# PCB-SCH_mvs.net
KiCad netlist of a schematic drawn in EAGLE
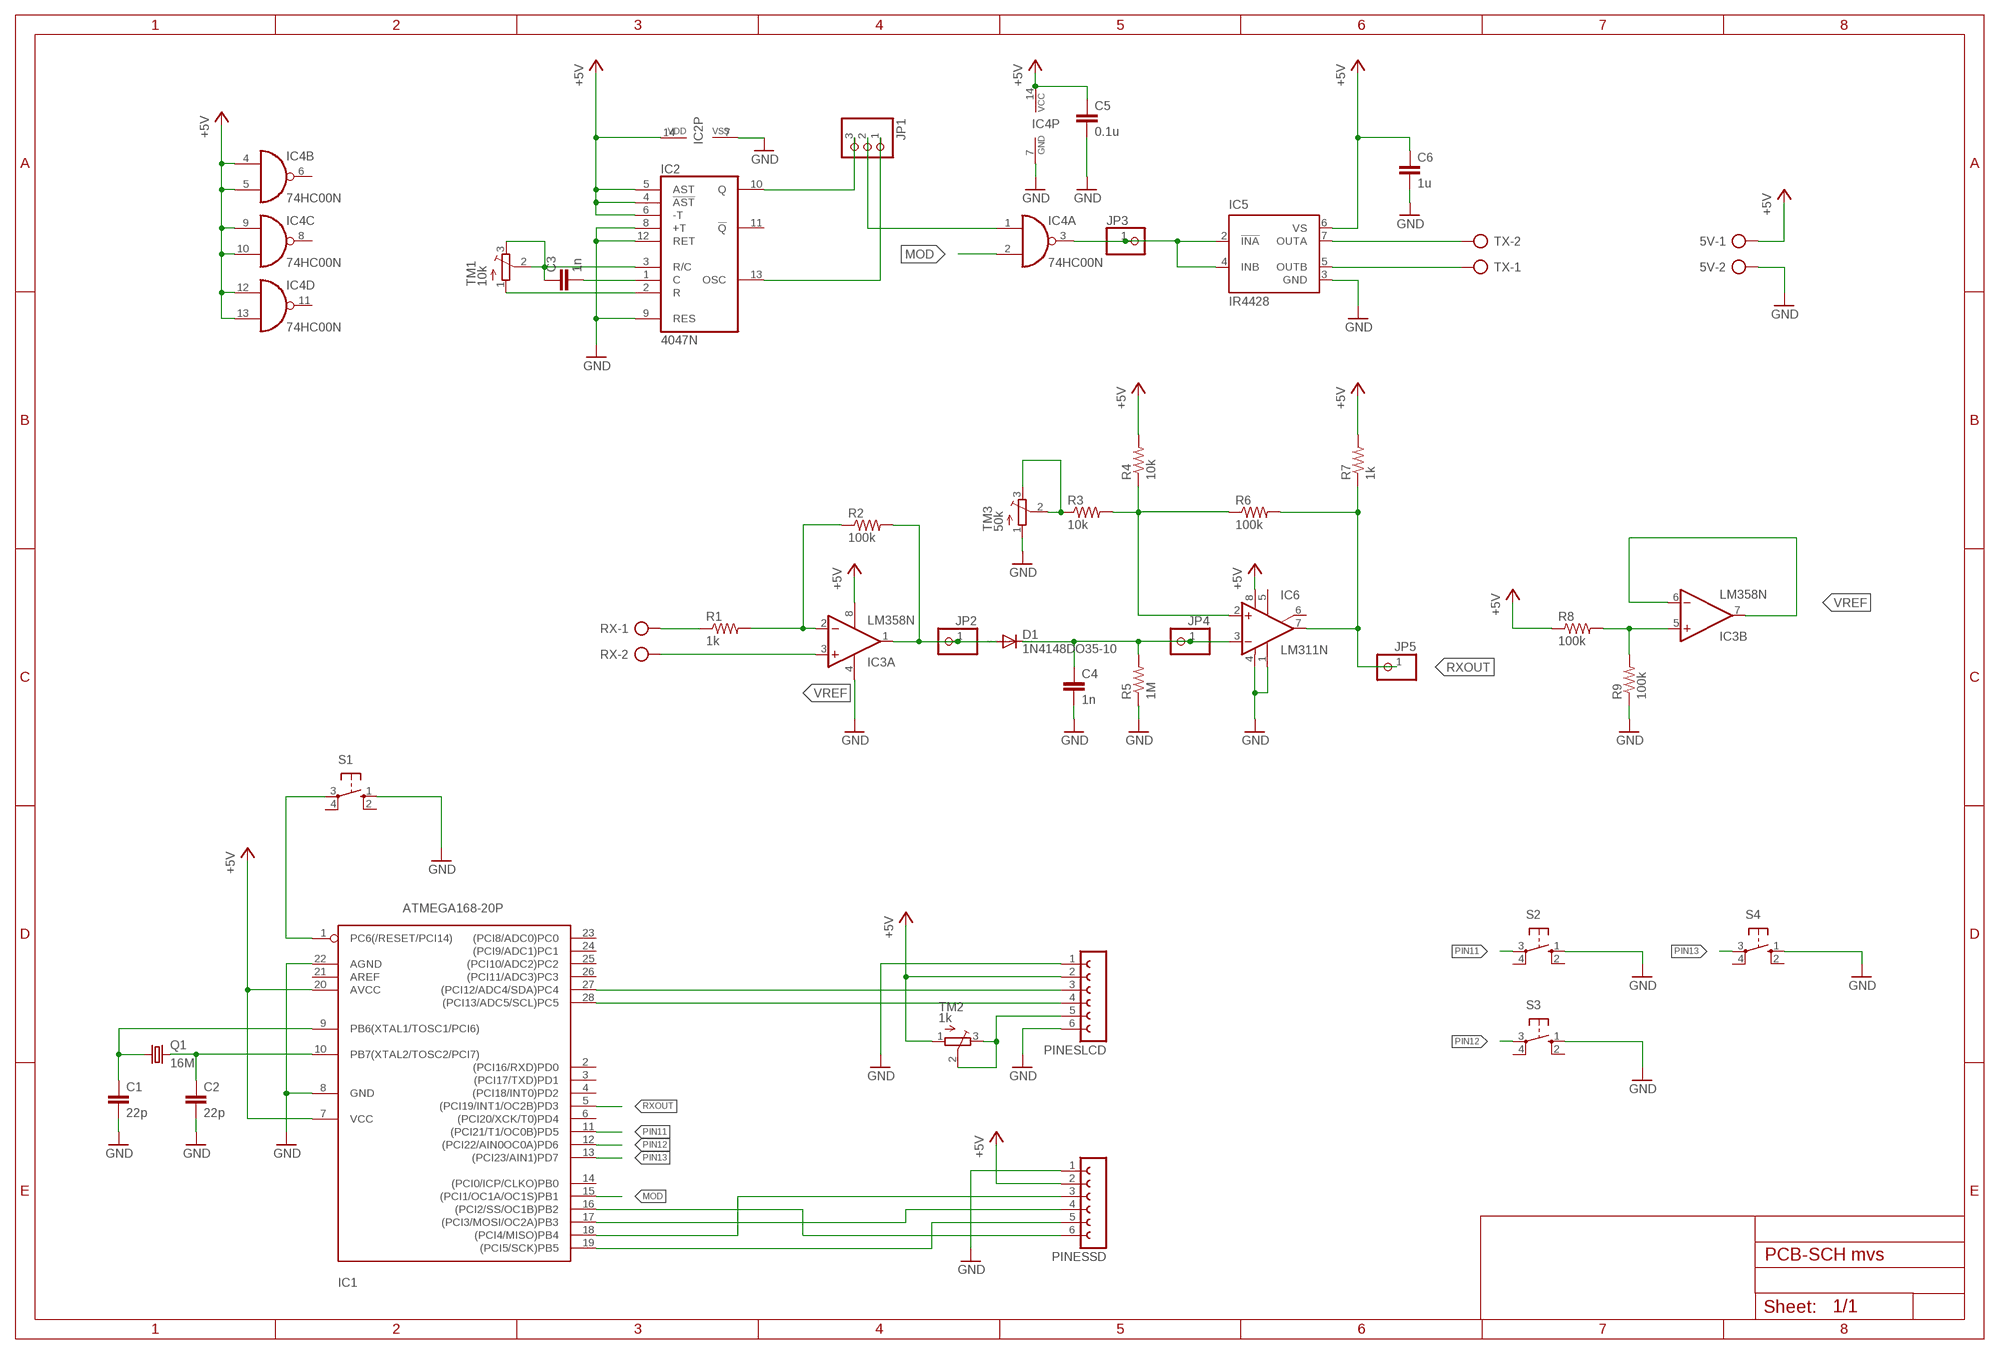
[diagram p0: schematic, sheet 1]

(export (version "E")
  (design (tool "Eeschema 10.0.6"))
  (components
    (comp (ref "5V")
      (value "AK500/2")
      (footprint "eagle-import:AK500_2")
      (libsource (lib "eagle-import") (part "AK500/2"))
    )
    (comp (ref "C1")
      (value "22p")
      (footprint "eagle-import:C050-024X044")
      (libsource (lib "eagle-import") (part "C-EU050-024X044"))
    )
    (comp (ref "C2")
      (value "22p")
      (footprint "eagle-import:C050-024X044")
      (libsource (lib "eagle-import") (part "C-EU050-024X044"))
    )
    (comp (ref "C3")
      (value "1n")
      (footprint "eagle-import:C050-024X044")
      (libsource (lib "eagle-import") (part "C-EU050-024X044"))
    )
    (comp (ref "C4")
      (value "1n")
      (footprint "eagle-import:C050-024X044")
      (libsource (lib "eagle-import") (part "C-EU050-024X044"))
    )
    (comp (ref "C5")
      (value "0.1u")
      (footprint "eagle-import:C050-024X044")
      (libsource (lib "eagle-import") (part "C-EU050-024X044"))
    )
    (comp (ref "C6")
      (value "1u")
      (footprint "eagle-import:C050-024X044")
      (libsource (lib "eagle-import") (part "C-EU050-024X044"))
    )
    (comp (ref "D1")
      (value "1N4148DO35-10")
      (footprint "eagle-import:DO35-10")
      (libsource (lib "eagle-import") (part "1N4148DO35-10"))
    )
    (comp (ref "IC1")
      (value "ATMEGA168-20P")
      (footprint "eagle-import:DIL28-3")
      (libsource (lib "eagle-import") (part "ATMEGA168P-20"))
    )
    (comp (ref "IC2")
      (value "4047N")
      (footprint "eagle-import:DIL14")
      (libsource (lib "eagle-import") (part "4047N"))
    )
    (comp (ref "IC3")
      (value "LM358N")
      (footprint "eagle-import:DIL08")
      (libsource (lib "eagle-import") (part "LM358N"))
    )
    (comp (ref "IC4")
      (value "74HC00N")
      (footprint "eagle-import:DIL14")
      (libsource (lib "eagle-import") (part "7400NHC"))
    )
    (comp (ref "IC5")
      (value "IR4428")
      (footprint "eagle-import:DIL08")
      (fields (field (name "MF") "INTERNATIONAL RECTIFIER(IR)") (field (name "MPN") "IR4428PBF"))
      (libsource (lib "eagle-import") (part "IR4428"))
    )
    (comp (ref "IC6")
      (value "LM311N")
      (footprint "eagle-import:DIL08")
      (libsource (lib "eagle-import") (part "LM311N"))
    )
    (comp (ref "JP1")
      (value "PINHD-1X3")
      (footprint "eagle-import:1X03")
      (libsource (lib "eagle-import") (part "PINHD-1X3"))
    )
    (comp (ref "JP2")
      (value "PINHD-1X1")
      (footprint "eagle-import:1X01")
      (libsource (lib "eagle-import") (part "PINHD-1X1"))
    )
    (comp (ref "JP3")
      (value "PINHD-1X1")
      (footprint "eagle-import:1X01")
      (libsource (lib "eagle-import") (part "PINHD-1X1"))
    )
    (comp (ref "JP4")
      (value "PINHD-1X1")
      (footprint "eagle-import:1X01")
      (libsource (lib "eagle-import") (part "PINHD-1X1"))
    )
    (comp (ref "JP5")
      (value "PINHD-1X1")
      (footprint "eagle-import:1X01")
      (libsource (lib "eagle-import") (part "PINHD-1X1"))
    )
    (comp (ref "PINESLCD")
      (value "FE06-1")
      (footprint "eagle-import:FE06")
      (libsource (lib "eagle-import") (part "FE06-1"))
    )
    (comp (ref "PINESSD")
      (value "FE06-1")
      (footprint "eagle-import:FE06")
      (libsource (lib "eagle-import") (part "FE06-1"))
    )
    (comp (ref "Q1")
      (value "16M")
      (footprint "eagle-import:HC49U-V")
      (libsource (lib "eagle-import") (part "CRYSTALHC49U-V"))
    )
    (comp (ref "R1")
      (value "1k")
      (footprint "eagle-import:0207_10")
      (libsource (lib "eagle-import") (part "R-US_0207/10"))
    )
    (comp (ref "R2")
      (value "100k")
      (footprint "eagle-import:0207_10")
      (libsource (lib "eagle-import") (part "R-US_0207/10"))
    )
    (comp (ref "R3")
      (value "10k")
      (footprint "eagle-import:0207_10")
      (libsource (lib "eagle-import") (part "R-US_0207/10"))
    )
    (comp (ref "R4")
      (value "10k")
      (footprint "eagle-import:0207_10")
      (libsource (lib "eagle-import") (part "R-US_0207/10"))
    )
    (comp (ref "R5")
      (value "1M")
      (footprint "eagle-import:0207_10")
      (libsource (lib "eagle-import") (part "R-US_0207/10"))
    )
    (comp (ref "R6")
      (value "100k")
      (footprint "eagle-import:0207_10")
      (libsource (lib "eagle-import") (part "R-US_0207/10"))
    )
    (comp (ref "R7")
      (value "1k")
      (footprint "eagle-import:0207_10")
      (libsource (lib "eagle-import") (part "R-US_0207/10"))
    )
    (comp (ref "R8")
      (value "100k")
      (footprint "eagle-import:0207_10")
      (libsource (lib "eagle-import") (part "R-US_0207/10"))
    )
    (comp (ref "R9")
      (value "100k")
      (footprint "eagle-import:0207_10")
      (libsource (lib "eagle-import") (part "R-US_0207/10"))
    )
    (comp (ref "RX")
      (value "AK500/2")
      (footprint "eagle-import:AK500_2")
      (libsource (lib "eagle-import") (part "AK500/2"))
    )
    (comp (ref "S1")
      (value "10-XX")
      (footprint "eagle-import:B3F-10XX")
      (fields (field (name "MPN") "B3F-1000"))
      (libsource (lib "eagle-import") (part "10-XX"))
    )
    (comp (ref "S2")
      (value "10-XX")
      (footprint "eagle-import:B3F-10XX")
      (fields (field (name "MPN") "B3F-1000"))
      (libsource (lib "eagle-import") (part "10-XX"))
    )
    (comp (ref "S3")
      (value "10-XX")
      (footprint "eagle-import:B3F-10XX")
      (fields (field (name "MPN") "B3F-1000"))
      (libsource (lib "eagle-import") (part "10-XX"))
    )
    (comp (ref "S4")
      (value "10-XX")
      (footprint "eagle-import:B3F-10XX")
      (fields (field (name "MPN") "B3F-1000"))
      (libsource (lib "eagle-import") (part "10-XX"))
    )
    (comp (ref "TM1")
      (value "10k")
      (footprint "eagle-import:TRIM-3386")
      (libsource (lib "eagle-import") (part "TRIMPOT3386"))
    )
    (comp (ref "TM2")
      (value "1k")
      (footprint "eagle-import:TRIM-3386")
      (libsource (lib "eagle-import") (part "TRIMPOT3386"))
    )
    (comp (ref "TM3")
      (value "50k")
      (footprint "eagle-import:TRIM-3386")
      (libsource (lib "eagle-import") (part "TRIMPOT3386"))
    )
    (comp (ref "TX")
      (value "AK500/2")
      (footprint "eagle-import:AK500_2")
      (libsource (lib "eagle-import") (part "AK500/2"))
    )
  )
  (nets
    (net (code "1") (name "+5V") (class "Default")
      (node (ref "5V") (pin "1") (pinfunction "KL_1") (pintype "passive"))
      (node (ref "C5") (pin "1") (pinfunction "1_1") (pintype "passive"))
      (node (ref "C6") (pin "1") (pinfunction "1_1") (pintype "passive"))
      (node (ref "IC1") (pin "20") (pinfunction "AVCC_20") (pintype "bidirectional"))
      (node (ref "IC1") (pin "7") (pinfunction "VCC_7") (pintype "bidirectional"))
      (node (ref "IC2") (pin "14") (pinfunction "VDD_14") (pintype "power_in"))
      (node (ref "IC2") (pin "4") (pinfunction "~{AST}_4") (pintype "input"))
      (node (ref "IC2") (pin "5") (pinfunction "AST_5") (pintype "input"))
      (node (ref "IC2") (pin "6") (pinfunction "-T_6") (pintype "input"))
      (node (ref "IC3") (pin "8") (pinfunction "V+_8") (pintype "power_in"))
      (node (ref "IC4") (pin "10") (pinfunction "I1_10") (pintype "input"))
      (node (ref "IC4") (pin "12") (pinfunction "I0_12") (pintype "input"))
      (node (ref "IC4") (pin "13") (pinfunction "I1_13") (pintype "input"))
      (node (ref "IC4") (pin "14") (pinfunction "VCC_14") (pintype "power_in"))
      (node (ref "IC4") (pin "4") (pinfunction "I0_4") (pintype "input"))
      (node (ref "IC4") (pin "5") (pinfunction "I1_5") (pintype "input"))
      (node (ref "IC4") (pin "9") (pinfunction "I0_9") (pintype "input"))
      (node (ref "IC5") (pin "6") (pinfunction "VS_6") (pintype "power_in"))
      (node (ref "IC6") (pin "8") (pinfunction "V+_8") (pintype "power_in"))
      (node (ref "PINESLCD") (pin "2") (pinfunction "2_2") (pintype "passive"))
      (node (ref "PINESSD") (pin "2") (pinfunction "2_2") (pintype "passive"))
      (node (ref "R4") (pin "2") (pinfunction "2_2") (pintype "passive"))
      (node (ref "R7") (pin "2") (pinfunction "2_2") (pintype "passive"))
      (node (ref "R8") (pin "1") (pinfunction "1_1") (pintype "passive"))
      (node (ref "TM2") (pin "1") (pinfunction "A_1") (pintype "passive"))
    )
    (net (code "2") (name "GND") (class "Default")
      (node (ref "5V") (pin "2") (pinfunction "KL_2") (pintype "passive"))
      (node (ref "C1") (pin "2") (pinfunction "2_2") (pintype "passive"))
      (node (ref "C2") (pin "2") (pinfunction "2_2") (pintype "passive"))
      (node (ref "C4") (pin "2") (pinfunction "2_2") (pintype "passive"))
      (node (ref "C5") (pin "2") (pinfunction "2_2") (pintype "passive"))
      (node (ref "C6") (pin "2") (pinfunction "2_2") (pintype "passive"))
      (node (ref "IC1") (pin "22") (pinfunction "AGND_22") (pintype "bidirectional"))
      (node (ref "IC1") (pin "8") (pinfunction "GND_8") (pintype "bidirectional"))
      (node (ref "IC2") (pin "12") (pinfunction "RET_12") (pintype "input"))
      (node (ref "IC2") (pin "7") (pinfunction "VSS_7") (pintype "power_in"))
      (node (ref "IC2") (pin "8") (pinfunction "+T_8") (pintype "input"))
      (node (ref "IC2") (pin "9") (pinfunction "RES_9") (pintype "input"))
      (node (ref "IC3") (pin "4") (pinfunction "V-_4") (pintype "power_in"))
      (node (ref "IC4") (pin "7") (pinfunction "GND_7") (pintype "power_in"))
      (node (ref "IC5") (pin "3") (pinfunction "GND_3") (pintype "power_in"))
      (node (ref "IC6") (pin "1") (pinfunction "GND_1") (pintype "passive"))
      (node (ref "IC6") (pin "4") (pinfunction "V-_4") (pintype "power_in"))
      (node (ref "PINESLCD") (pin "1") (pinfunction "1_1") (pintype "passive"))
      (node (ref "PINESLCD") (pin "6") (pinfunction "6_6") (pintype "passive"))
      (node (ref "PINESSD") (pin "1") (pinfunction "1_1") (pintype "passive"))
      (node (ref "R5") (pin "1") (pinfunction "1_1") (pintype "passive"))
      (node (ref "R9") (pin "1") (pinfunction "1_1") (pintype "passive"))
      (node (ref "S1") (pin "1") (pinfunction "S_1") (pintype "passive"))
      (node (ref "S2") (pin "1") (pinfunction "S_1") (pintype "passive"))
      (node (ref "S3") (pin "1") (pinfunction "S_1") (pintype "passive"))
      (node (ref "S4") (pin "1") (pinfunction "S_1") (pintype "passive"))
      (node (ref "TM3") (pin "1") (pinfunction "A_1") (pintype "passive"))
    )
    (net (code "3") (name "MOD") (class "Default")
      (node (ref "IC1") (pin "15") (pinfunction "(PCI1/OC1A/OC1S)PB1_15") (pintype "bidirectional"))
      (node (ref "IC4") (pin "2") (pinfunction "I1_2") (pintype "input"))
    )
    (net (code "4") (name "Net-(IC1-(PCI2{slash}SS{slash}OC1B)PB2)") (class "Default")
      (node (ref "IC1") (pin "16") (pinfunction "(PCI2/SS/OC1B)PB2_16") (pintype "bidirectional"))
      (node (ref "PINESSD") (pin "6") (pinfunction "6_6") (pintype "passive"))
    )
    (net (code "5") (name "Net-(IC1-(PCI3{slash}MOSI{slash}OC2A)PB3)") (class "Default")
      (node (ref "IC1") (pin "17") (pinfunction "(PCI3/MOSI/OC2A)PB3_17") (pintype "bidirectional"))
      (node (ref "PINESSD") (pin "4") (pinfunction "4_4") (pintype "passive"))
    )
    (net (code "6") (name "Net-(IC1-(PCI4{slash}MISO)PB4)") (class "Default")
      (node (ref "IC1") (pin "18") (pinfunction "(PCI4/MISO)PB4_18") (pintype "bidirectional"))
      (node (ref "PINESSD") (pin "3") (pinfunction "3_3") (pintype "passive"))
    )
    (net (code "7") (name "Net-(IC1-(PCI5{slash}SCK)PB5)") (class "Default")
      (node (ref "IC1") (pin "19") (pinfunction "(PCI5/SCK)PB5_19") (pintype "bidirectional"))
      (node (ref "PINESSD") (pin "5") (pinfunction "5_5") (pintype "passive"))
    )
    (net (code "8") (name "Net-(IC1-(PCI12{slash}ADC4{slash}SDA)PC4)") (class "Default")
      (node (ref "IC1") (pin "27") (pinfunction "(PCI12/ADC4/SDA)PC4_27") (pintype "bidirectional"))
      (node (ref "PINESLCD") (pin "3") (pinfunction "3_3") (pintype "passive"))
    )
    (net (code "9") (name "Net-(IC1-(PCI13{slash}ADC5{slash}SCL)PC5)") (class "Default")
      (node (ref "IC1") (pin "28") (pinfunction "(PCI13/ADC5/SCL)PC5_28") (pintype "bidirectional"))
      (node (ref "PINESLCD") (pin "4") (pinfunction "4_4") (pintype "passive"))
    )
    (net (code "10") (name "Net-(IC1-PB6(XTAL1{slash}TOSC1{slash}PCI6))") (class "Default")
      (node (ref "C1") (pin "1") (pinfunction "1_1") (pintype "passive"))
      (node (ref "IC1") (pin "9") (pinfunction "PB6(XTAL1/TOSC1/PCI6)_9") (pintype "bidirectional"))
      (node (ref "Q1") (pin "1") (pinfunction "1_1") (pintype "passive"))
    )
    (net (code "11") (name "Net-(IC1-PB7(XTAL2{slash}TOSC2{slash}PCI7))") (class "Default")
      (node (ref "C2") (pin "1") (pinfunction "1_1") (pintype "passive"))
      (node (ref "IC1") (pin "10") (pinfunction "PB7(XTAL2/TOSC2/PCI7)_10") (pintype "bidirectional"))
      (node (ref "Q1") (pin "2") (pinfunction "2_2") (pintype "passive"))
    )
    (net (code "12") (name "Net-(IC1-PC6({slash}RESET{slash}PCI14))") (class "Default")
      (node (ref "IC1") (pin "1") (pinfunction "PC6(/RESET/PCI14)_1") (pintype "bidirectional"))
      (node (ref "S1") (pin "3") (pinfunction "P_3") (pintype "passive"))
    )
    (net (code "13") (name "Net-(IC2A-C)") (class "Default")
      (node (ref "C3") (pin "2") (pinfunction "2_2") (pintype "passive"))
      (node (ref "IC2") (pin "1") (pinfunction "C_1") (pintype "input"))
    )
    (net (code "14") (name "Net-(IC2A-OSC)") (class "Default")
      (node (ref "IC2") (pin "13") (pinfunction "OSC_13") (pintype "output"))
      (node (ref "JP1") (pin "1") (pinfunction "1_1") (pintype "passive"))
    )
    (net (code "15") (name "Net-(IC2A-Q)") (class "Default")
      (node (ref "IC2") (pin "10") (pinfunction "Q_10") (pintype "output"))
      (node (ref "JP1") (pin "3") (pinfunction "3_3") (pintype "passive"))
    )
    (net (code "16") (name "Net-(IC2A-R)") (class "Default")
      (node (ref "IC2") (pin "2") (pinfunction "R_2") (pintype "input"))
      (node (ref "TM1") (pin "1") (pinfunction "A_1") (pintype "passive"))
    )
    (net (code "17") (name "Net-(IC2A-R{slash}C)") (class "Default")
      (node (ref "C3") (pin "1") (pinfunction "1_1") (pintype "passive"))
      (node (ref "IC2") (pin "3") (pinfunction "R/C_3") (pintype "input"))
      (node (ref "TM1") (pin "2") (pinfunction "S_2") (pintype "passive"))
      (node (ref "TM1") (pin "3") (pinfunction "E_3") (pintype "passive"))
    )
    (net (code "18") (name "Net-(IC3A--IN)") (class "Default")
      (node (ref "IC3") (pin "2") (pinfunction "-IN_2") (pintype "input"))
      (node (ref "R1") (pin "2") (pinfunction "2_2") (pintype "passive"))
      (node (ref "R2") (pin "1") (pinfunction "1_1") (pintype "passive"))
    )
    (net (code "19") (name "Net-(IC3A-OUT)") (class "Default")
      (node (ref "D1") (pin "A") (pinfunction "A_A") (pintype "passive"))
      (node (ref "IC3") (pin "1") (pinfunction "OUT_1") (pintype "output"))
      (node (ref "JP2") (pin "1") (pinfunction "1_1") (pintype "passive"))
      (node (ref "R2") (pin "2") (pinfunction "2_2") (pintype "passive"))
    )
    (net (code "20") (name "Net-(IC3B-+IN)") (class "Default")
      (node (ref "IC3") (pin "5") (pinfunction "+IN_5") (pintype "input"))
      (node (ref "R8") (pin "2") (pinfunction "2_2") (pintype "passive"))
      (node (ref "R9") (pin "2") (pinfunction "2_2") (pintype "passive"))
    )
    (net (code "21") (name "Net-(IC4A-I0)") (class "Default")
      (node (ref "IC4") (pin "1") (pinfunction "I0_1") (pintype "input"))
      (node (ref "JP1") (pin "2") (pinfunction "2_2") (pintype "passive"))
    )
    (net (code "22") (name "Net-(IC4A-O)") (class "Default")
      (node (ref "IC4") (pin "3") (pinfunction "O_3") (pintype "output"))
      (node (ref "IC5") (pin "2") (pinfunction "~{INA}_2") (pintype "input"))
      (node (ref "IC5") (pin "4") (pinfunction "INB_4") (pintype "input"))
      (node (ref "JP3") (pin "1") (pinfunction "1_1") (pintype "passive"))
    )
    (net (code "23") (name "Net-(IC5-OUTA)") (class "Default")
      (node (ref "IC5") (pin "7") (pinfunction "OUTA_7") (pintype "output"))
      (node (ref "TX") (pin "2") (pinfunction "KL_2") (pintype "passive"))
    )
    (net (code "24") (name "Net-(IC5-OUTB)") (class "Default")
      (node (ref "IC5") (pin "5") (pinfunction "OUTB_5") (pintype "output"))
      (node (ref "TX") (pin "1") (pinfunction "KL_1") (pintype "passive"))
    )
    (net (code "25") (name "Net-(IC6-+IN)") (class "Default")
      (node (ref "IC6") (pin "2") (pinfunction "+IN_2") (pintype "input"))
      (node (ref "R3") (pin "2") (pinfunction "2_2") (pintype "passive"))
      (node (ref "R4") (pin "1") (pinfunction "1_1") (pintype "passive"))
      (node (ref "R6") (pin "1") (pinfunction "1_1") (pintype "passive"))
    )
    (net (code "26") (name "Net-(IC6--IN)") (class "Default")
      (node (ref "C4") (pin "1") (pinfunction "1_1") (pintype "passive"))
      (node (ref "D1") (pin "C") (pinfunction "C_C") (pintype "passive"))
      (node (ref "IC6") (pin "3") (pinfunction "-IN_3") (pintype "input"))
      (node (ref "JP4") (pin "1") (pinfunction "1_1") (pintype "passive"))
      (node (ref "R5") (pin "2") (pinfunction "2_2") (pintype "passive"))
    )
    (net (code "27") (name "Net-(RXA-KL)") (class "Default")
      (node (ref "R1") (pin "1") (pinfunction "1_1") (pintype "passive"))
      (node (ref "RX") (pin "1") (pinfunction "KL_1") (pintype "passive"))
    )
    (net (code "28") (name "Net-(TM2-E)") (class "Default")
      (node (ref "PINESLCD") (pin "5") (pinfunction "5_5") (pintype "passive"))
      (node (ref "TM2") (pin "2") (pinfunction "S_2") (pintype "passive"))
      (node (ref "TM2") (pin "3") (pinfunction "E_3") (pintype "passive"))
    )
    (net (code "29") (name "Net-(TM3-E)") (class "Default")
      (node (ref "R3") (pin "1") (pinfunction "1_1") (pintype "passive"))
      (node (ref "TM3") (pin "2") (pinfunction "S_2") (pintype "passive"))
      (node (ref "TM3") (pin "3") (pinfunction "E_3") (pintype "passive"))
    )
    (net (code "30") (name "PIN11") (class "Default")
      (node (ref "IC1") (pin "11") (pinfunction "(PCI21/T1/OC0B)PD5_11") (pintype "bidirectional"))
      (node (ref "S2") (pin "3") (pinfunction "P_3") (pintype "passive"))
    )
    (net (code "31") (name "PIN12") (class "Default")
      (node (ref "IC1") (pin "12") (pinfunction "(PCI22/AIN0OC0A)PD6_12") (pintype "bidirectional"))
      (node (ref "S3") (pin "3") (pinfunction "P_3") (pintype "passive"))
    )
    (net (code "32") (name "PIN13") (class "Default")
      (node (ref "IC1") (pin "13") (pinfunction "(PCI23/AIN1)PD7_13") (pintype "bidirectional"))
      (node (ref "S4") (pin "3") (pinfunction "P_3") (pintype "passive"))
    )
    (net (code "33") (name "RXOUT") (class "Default")
      (node (ref "IC1") (pin "5") (pinfunction "(PCI19/INT1/OC2B)PD3_5") (pintype "bidirectional"))
      (node (ref "IC6") (pin "7") (pinfunction "OUT_7") (pintype "output"))
      (node (ref "JP5") (pin "1") (pinfunction "1_1") (pintype "passive"))
      (node (ref "R6") (pin "2") (pinfunction "2_2") (pintype "passive"))
      (node (ref "R7") (pin "1") (pinfunction "1_1") (pintype "passive"))
    )
    (net (code "34") (name "VREF") (class "Default")
      (node (ref "IC3") (pin "3") (pinfunction "+IN_3") (pintype "input"))
      (node (ref "IC3") (pin "6") (pinfunction "-IN_6") (pintype "input"))
      (node (ref "IC3") (pin "7") (pinfunction "OUT_7") (pintype "output"))
      (node (ref "RX") (pin "2") (pinfunction "KL_2") (pintype "passive"))
    )
    (net (code "35") (name "unconnected-(IC1-(PCI0{slash}ICP{slash}CLKO)PB0-Pad14)") (class "Default")
      (node (ref "IC1") (pin "14") (pinfunction "(PCI0/ICP/CLKO)PB0_14") (pintype "bidirectional"))
    )
    (net (code "36") (name "unconnected-(IC1-(PCI8{slash}ADC0)PC0-Pad23)") (class "Default")
      (node (ref "IC1") (pin "23") (pinfunction "(PCI8/ADC0)PC0_23") (pintype "bidirectional"))
    )
    (net (code "37") (name "unconnected-(IC1-(PCI9{slash}ADC1)PC1-Pad24)") (class "Default")
      (node (ref "IC1") (pin "24") (pinfunction "(PCI9/ADC1)PC1_24") (pintype "bidirectional"))
    )
    (net (code "38") (name "unconnected-(IC1-(PCI10{slash}ADC2)PC2-Pad25)") (class "Default")
      (node (ref "IC1") (pin "25") (pinfunction "(PCI10/ADC2)PC2_25") (pintype "bidirectional"))
    )
    (net (code "39") (name "unconnected-(IC1-(PCI11{slash}ADC3)PC3-Pad26)") (class "Default")
      (node (ref "IC1") (pin "26") (pinfunction "(PCI11/ADC3)PC3_26") (pintype "bidirectional"))
    )
    (net (code "40") (name "unconnected-(IC1-(PCI16{slash}RXD)PD0-Pad2)") (class "Default")
      (node (ref "IC1") (pin "2") (pinfunction "(PCI16/RXD)PD0_2") (pintype "bidirectional"))
    )
    (net (code "41") (name "unconnected-(IC1-(PCI17{slash}TXD)PD1-Pad3)") (class "Default")
      (node (ref "IC1") (pin "3") (pinfunction "(PCI17/TXD)PD1_3") (pintype "bidirectional"))
    )
    (net (code "42") (name "unconnected-(IC1-(PCI18{slash}INT0)PD2-Pad4)") (class "Default")
      (node (ref "IC1") (pin "4") (pinfunction "(PCI18/INT0)PD2_4") (pintype "bidirectional"))
    )
    (net (code "43") (name "unconnected-(IC1-(PCI20{slash}XCK{slash}T0)PD4-Pad6)") (class "Default")
      (node (ref "IC1") (pin "6") (pinfunction "(PCI20/XCK/T0)PD4_6") (pintype "bidirectional"))
    )
    (net (code "44") (name "unconnected-(IC1-AREF-Pad21)") (class "Default")
      (node (ref "IC1") (pin "21") (pinfunction "AREF_21") (pintype "bidirectional"))
    )
    (net (code "45") (name "unconnected-(IC2A-~{Q}-Pad11)") (class "Default")
      (node (ref "IC2") (pin "11") (pinfunction "~{Q}_11") (pintype "output"))
    )
    (net (code "46") (name "unconnected-(IC4B-O-Pad6)") (class "Default")
      (node (ref "IC4") (pin "6") (pinfunction "O_6") (pintype "output"))
    )
    (net (code "47") (name "unconnected-(IC4C-O-Pad8)") (class "Default")
      (node (ref "IC4") (pin "8") (pinfunction "O_8") (pintype "output"))
    )
    (net (code "48") (name "unconnected-(IC4D-O-Pad11)") (class "Default")
      (node (ref "IC4") (pin "11") (pinfunction "O_11") (pintype "output"))
    )
    (net (code "49") (name "unconnected-(IC6-ON-Pad5)") (class "Default")
      (node (ref "IC6") (pin "5") (pinfunction "ON_5") (pintype "passive"))
    )
    (net (code "50") (name "unconnected-(IC6-ON{slash}STR-Pad6)") (class "Default")
      (node (ref "IC6") (pin "6") (pinfunction "ON/STR_6") (pintype "passive"))
    )
    (net (code "51") (name "unconnected-(S1-P1-Pad4)") (class "Default")
      (node (ref "S1") (pin "4") (pinfunction "P1_4") (pintype "passive"))
    )
    (net (code "52") (name "unconnected-(S1-S1-Pad2)") (class "Default")
      (node (ref "S1") (pin "2") (pinfunction "S1_2") (pintype "passive"))
    )
    (net (code "53") (name "unconnected-(S2-P1-Pad4)") (class "Default")
      (node (ref "S2") (pin "4") (pinfunction "P1_4") (pintype "passive"))
    )
    (net (code "54") (name "unconnected-(S2-S1-Pad2)") (class "Default")
      (node (ref "S2") (pin "2") (pinfunction "S1_2") (pintype "passive"))
    )
    (net (code "55") (name "unconnected-(S3-P1-Pad4)") (class "Default")
      (node (ref "S3") (pin "4") (pinfunction "P1_4") (pintype "passive"))
    )
    (net (code "56") (name "unconnected-(S3-S1-Pad2)") (class "Default")
      (node (ref "S3") (pin "2") (pinfunction "S1_2") (pintype "passive"))
    )
    (net (code "57") (name "unconnected-(S4-P1-Pad4)") (class "Default")
      (node (ref "S4") (pin "4") (pinfunction "P1_4") (pintype "passive"))
    )
    (net (code "58") (name "unconnected-(S4-S1-Pad2)") (class "Default")
      (node (ref "S4") (pin "2") (pinfunction "S1_2") (pintype "passive"))
    )
  )
)
